# ActuatorMKII_Torpedoes.net
KiCad netlist of a schematic drawn in Altium Designer
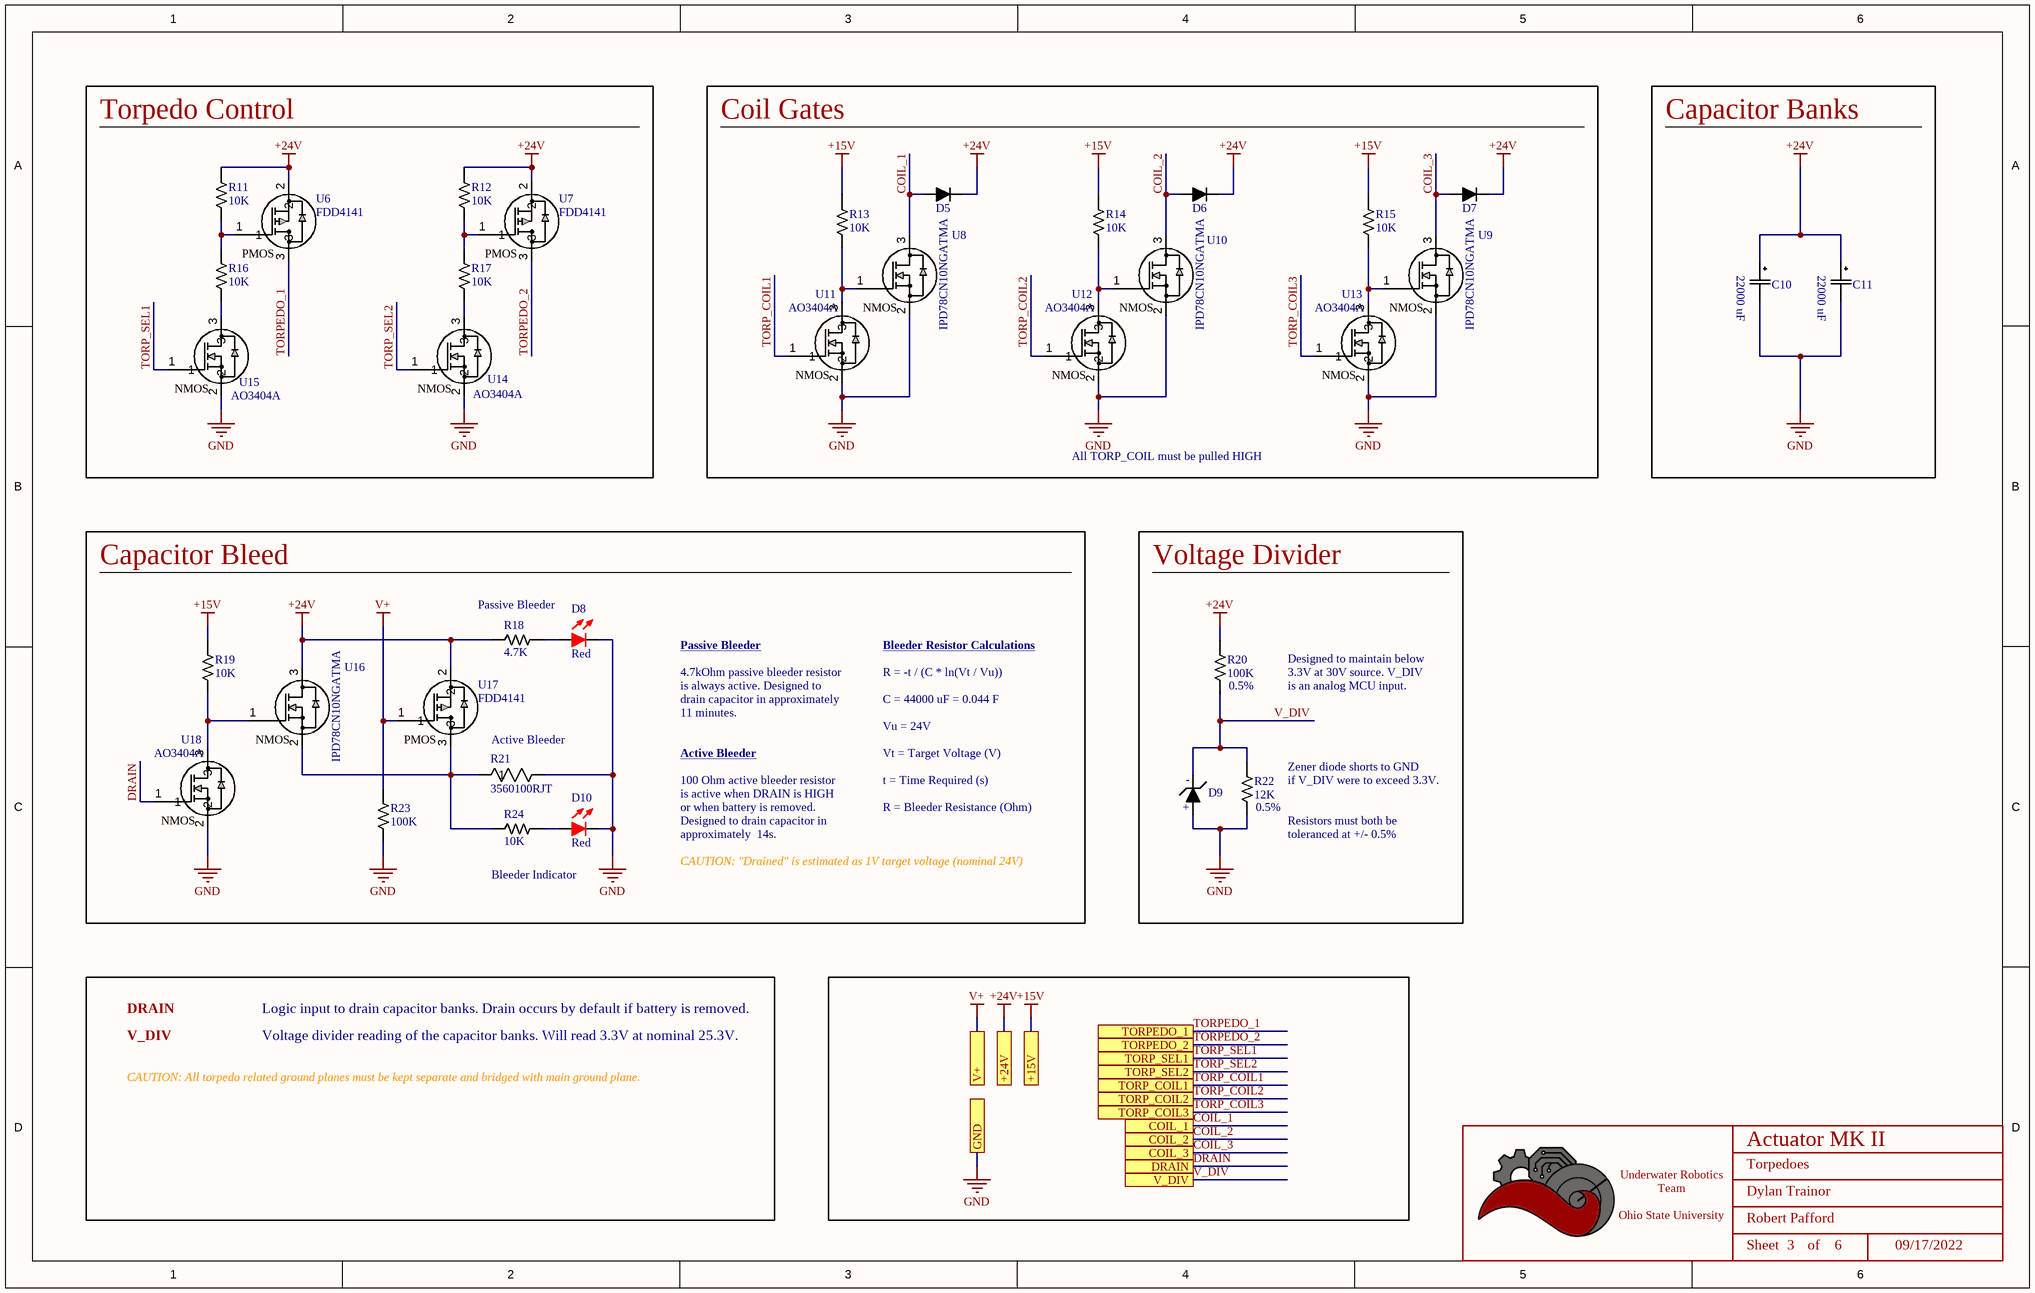
[diagram p0: ActuatorMKII_Torpedoes.SchDoc]

(export (version "E")
  (design (tool "Eeschema 10.0.6"))
  (components
    (comp (ref "C10")
      (value "Cap 22000uF 22V +/-20% Aluminum")
      (footprint "UVK1E223MRD_RA")
      (description "Cap 22000uF 25V 20% Aluminum Radial Through Hole")
      (fields (field (name "MADE BY") "Cole Davis") (field (name "VERIFIED BY") "Name"))
      (libsource (lib "Capacitors") (part "CAPACITOR_22000uF_Radial"))
    )
    (comp (ref "C11")
      (value "Cap 22000uF 22V +/-20% Aluminum")
      (footprint "UVK1E223MRD_RA")
      (description "Cap 22000uF 25V 20% Aluminum Radial Through Hole")
      (fields (field (name "MADE BY") "Cole Davis") (field (name "VERIFIED BY") "Name"))
      (libsource (lib "Capacitors") (part "CAPACITOR_22000uF_Radial"))
    )
    (comp (ref "D5")
      (value "B330-13-F")
      (footprint "DO-214AB")
      (description "Schottky Diode, 30V reverse breakdown, 3A, Vf = 0.500V")
      (fields (field (name "MADE BY") "Tyson N."))
      (libsource (lib "Diodes") (part "SCHOTTKY_30V_3A"))
    )
    (comp (ref "D6")
      (value "B330-13-F")
      (footprint "DO-214AB")
      (description "Schottky Diode, 30V reverse breakdown, 3A, Vf = 0.500V")
      (fields (field (name "MADE BY") "Tyson N."))
      (libsource (lib "Diodes") (part "SCHOTTKY_30V_3A"))
    )
    (comp (ref "D7")
      (value "B330-13-F")
      (footprint "DO-214AB")
      (description "Schottky Diode, 30V reverse breakdown, 3A, Vf = 0.500V")
      (fields (field (name "MADE BY") "Tyson N."))
      (libsource (lib "Diodes") (part "SCHOTTKY_30V_3A"))
    )
    (comp (ref "D8")
      (value "150060RS75000")
      (footprint "LED_0603")
      (description "LED Red Vf= 2V If = 0.020A\r\n150060RS75000")
      (fields (field (name "COLOR") "Red") (field (name "MADE BY") "Robert Pafford"))
      (libsource (lib "Diodes") (part "LED_Red_0603"))
    )
    (comp (ref "D9")
      (value "Zener_Diode_3.3V_250mW_1")
      (footprint "SOD-123")
      (description "Zener Diode ¦ 3.3 V ¦ 250 mW ¦ SOT-23")
      (fields (field (name "POWER") "410mW") (field (name "MADE BY") "Nathan A"))
      (libsource (lib "Diodes") (part "Zener_Diode_3.3V_250mW_1"))
    )
    (comp (ref "D10")
      (value "150060RS75000")
      (footprint "LED_0603")
      (description "LED Red Vf= 2V If = 0.020A\r\n150060RS75000")
      (fields (field (name "COLOR") "Red") (field (name "MADE BY") "Robert Pafford"))
      (libsource (lib "Diodes") (part "LED_Red_0603"))
    )
    (comp (ref "R11")
      (value "10k Ohm 5% 1/10W")
      (footprint "RESISTOR_0603")
      (description "RES 10k OHM 5% 1/10W 0603")
      (fields
        (field (name "TOLERANCE") "+/- 5%")
        (field (name "VALUE  (OHMS)") "10K")
        (field (name "MADE BY") "Robert Pafford")
      )
      (libsource (lib "Resistors") (part "RESISTOR_10K_0603"))
    )
    (comp (ref "R12")
      (value "10k Ohm 5% 1/10W")
      (footprint "RESISTOR_0603")
      (description "RES 10k OHM 5% 1/10W 0603")
      (fields
        (field (name "TOLERANCE") "+/- 5%")
        (field (name "VALUE  (OHMS)") "10K")
        (field (name "MADE BY") "Robert Pafford")
      )
      (libsource (lib "Resistors") (part "RESISTOR_10K_0603"))
    )
    (comp (ref "R13")
      (value "10k Ohm 5% 1/10W")
      (footprint "RESISTOR_0603")
      (description "RES 10k OHM 5% 1/10W 0603")
      (fields
        (field (name "TOLERANCE") "+/- 5%")
        (field (name "VALUE  (OHMS)") "10K")
        (field (name "MADE BY") "Robert Pafford")
      )
      (libsource (lib "Resistors") (part "RESISTOR_10K_0603"))
    )
    (comp (ref "R14")
      (value "10k Ohm 5% 1/10W")
      (footprint "RESISTOR_0603")
      (description "RES 10k OHM 5% 1/10W 0603")
      (fields
        (field (name "TOLERANCE") "+/- 5%")
        (field (name "VALUE  (OHMS)") "10K")
        (field (name "MADE BY") "Robert Pafford")
      )
      (libsource (lib "Resistors") (part "RESISTOR_10K_0603"))
    )
    (comp (ref "R15")
      (value "10k Ohm 5% 1/10W")
      (footprint "RESISTOR_0603")
      (description "RES 10k OHM 5% 1/10W 0603")
      (fields
        (field (name "TOLERANCE") "+/- 5%")
        (field (name "VALUE  (OHMS)") "10K")
        (field (name "MADE BY") "Robert Pafford")
      )
      (libsource (lib "Resistors") (part "RESISTOR_10K_0603"))
    )
    (comp (ref "R16")
      (value "10k Ohm 5% 1/10W")
      (footprint "RESISTOR_0603")
      (description "RES 10k OHM 5% 1/10W 0603")
      (fields
        (field (name "TOLERANCE") "+/- 5%")
        (field (name "VALUE  (OHMS)") "10K")
        (field (name "MADE BY") "Robert Pafford")
      )
      (libsource (lib "Resistors") (part "RESISTOR_10K_0603"))
    )
    (comp (ref "R17")
      (value "10k Ohm 5% 1/10W")
      (footprint "RESISTOR_0603")
      (description "RES 10k OHM 5% 1/10W 0603")
      (fields
        (field (name "TOLERANCE") "+/- 5%")
        (field (name "VALUE  (OHMS)") "10K")
        (field (name "MADE BY") "Robert Pafford")
      )
      (libsource (lib "Resistors") (part "RESISTOR_10K_0603"))
    )
    (comp (ref "R18")
      (value "4.7k Ohm 5% 1/10W")
      (footprint "RESISTOR_0603")
      (description "RES 4.7k OHM 5% 1/10W 0603")
      (fields
        (field (name "TOLERANCE") "+/- 5%")
        (field (name "VALUE  (OHMS)") "4.7K")
        (field (name "MADE BY") "Robert Pafford")
      )
      (libsource (lib "Resistors") (part "RESISTOR_4.7K_0603"))
    )
    (comp (ref "R19")
      (value "10k Ohm 5% 1/10W")
      (footprint "RESISTOR_0603")
      (description "RES 10k OHM 5% 1/10W 0603")
      (fields
        (field (name "TOLERANCE") "+/- 5%")
        (field (name "VALUE  (OHMS)") "10K")
        (field (name "MADE BY") "Robert Pafford")
      )
      (libsource (lib "Resistors") (part "RESISTOR_10K_0603"))
    )
    (comp (ref "R20")
      (value "100k Ohm 0.5% 1/10W")
      (footprint "RESISTOR_0603")
      (description "RES 100k OHM 0.5% 1/10W 0603")
      (fields
        (field (name "TOLERANCE") "+/- 0.5%")
        (field (name "VALUE  (OHMS)") "100K")
        (field (name "MADE BY") "John Ulm")
      )
      (libsource (lib "Resistors") (part "RESISTOR_100K_0.5%_0603"))
    )
    (comp (ref "R21")
      (value "3560100RJT")
      (footprint "RES_3550_TEC")
      (description "RES 35601 100R 6W 5%")
      (fields
        (field (name "MANUFACTURER_PART_NUMBER") "3550120RJT")
        (field (name "COPYRIGHT") "Copyright (C) 2022 Ultra Librarian. All rights reserved.")
      )
      (libsource (lib "Resistors") (part "3560100RJT"))
    )
    (comp (ref "R22")
      (value "12k Ohm 0.5% 1/10W")
      (footprint "RESISTOR_0603")
      (description "RES 12k OHM 0.5% 1/10W 0603")
      (fields
        (field (name "TOLERANCE") "+/- 0.5%")
        (field (name "VALUE  (OHMS)") "12K")
        (field (name "MADE BY") "John Ulm")
      )
      (libsource (lib "Resistors") (part "RESISTOR_12K_0.5%_0603"))
    )
    (comp (ref "R23")
      (value "100k Ohm 5% 1/8W")
      (footprint "RESISTOR_0603")
      (description "RES 100k OHM 5% 1/10W 0603")
      (fields
        (field (name "TOLERANCE") "+/- 5%")
        (field (name "VALUE  (OHMS)") "100K")
        (field (name "MADE BY") "Flip B")
      )
      (libsource (lib "Resistors") (part "RESISTOR_100K_0603_1"))
    )
    (comp (ref "R24")
      (value "10k Ohm 5% 1/10W")
      (footprint "RESISTOR_0603")
      (description "RES 10k OHM 5% 1/10W 0603")
      (fields
        (field (name "TOLERANCE") "+/- 5%")
        (field (name "VALUE  (OHMS)") "10K")
        (field (name "MADE BY") "Robert Pafford")
      )
      (libsource (lib "Resistors") (part "RESISTOR_10K_0603"))
    )
    (comp (ref "U6")
      (value "FDD4141")
      (footprint "DPAK_ONS")
      (description "P-Channel 10.8A (Ta), 50A (Tc) 2.4W (Ta), 69W (Tc) Surface Mount D-PAK (TO-252AA)")
      (fields (field (name "CREATED BY") "Dylan T"))
      (libsource (lib "Transistors") (part "FDD4141"))
    )
    (comp (ref "U7")
      (value "FDD4141")
      (footprint "DPAK_ONS")
      (description "P-Channel 10.8A (Ta), 50A (Tc) 2.4W (Ta), 69W (Tc) Surface Mount D-PAK (TO-252AA)")
      (fields (field (name "CREATED BY") "Dylan T"))
      (libsource (lib "Transistors") (part "FDD4141"))
    )
    (comp (ref "U8")
      (value "MOSFET N-Ch 100V 13A TO252-3")
      (footprint "DPAK_ONS")
      (description "N-Channel 100 V 13A (Tc) 31W (Tc) Surface Mount PG-TO252-3")
      (fields (field (name "CREATED BY") "John Ulm") (field (name "VERIFIED BY") "----"))
      (libsource (lib "Transistors") (part "IPD78CN10NGATMA1"))
    )
    (comp (ref "U9")
      (value "MOSFET N-Ch 100V 13A TO252-3")
      (footprint "DPAK_ONS")
      (description "N-Channel 100 V 13A (Tc) 31W (Tc) Surface Mount PG-TO252-3")
      (fields (field (name "CREATED BY") "John Ulm") (field (name "VERIFIED BY") "----"))
      (libsource (lib "Transistors") (part "IPD78CN10NGATMA1"))
    )
    (comp (ref "U10")
      (value "MOSFET N-Ch 100V 13A TO252-3")
      (footprint "DPAK_ONS")
      (description "N-Channel 100 V 13A (Tc) 31W (Tc) Surface Mount PG-TO252-3")
      (fields (field (name "CREATED BY") "John Ulm") (field (name "VERIFIED BY") "----"))
      (libsource (lib "Transistors") (part "IPD78CN10NGATMA1"))
    )
    (comp (ref "U11")
      (value "AO3404A")
      (footprint "SOT-23-3")
      (description "N-Channel 30 V 5.8A (Ta) 1.4W (Ta) Surface Mount SOT-23-3")
      (fields (field (name "CREATED BY") "Dylan T"))
      (libsource (lib "Transistors") (part "AO3404A"))
    )
    (comp (ref "U12")
      (value "AO3404A")
      (footprint "SOT-23-3")
      (description "N-Channel 30 V 5.8A (Ta) 1.4W (Ta) Surface Mount SOT-23-3")
      (fields (field (name "CREATED BY") "Dylan T"))
      (libsource (lib "Transistors") (part "AO3404A"))
    )
    (comp (ref "U13")
      (value "AO3404A")
      (footprint "SOT-23-3")
      (description "N-Channel 30 V 5.8A (Ta) 1.4W (Ta) Surface Mount SOT-23-3")
      (fields (field (name "CREATED BY") "Dylan T"))
      (libsource (lib "Transistors") (part "AO3404A"))
    )
    (comp (ref "U14")
      (value "AO3404A")
      (footprint "SOT-23-3")
      (description "N-Channel 30 V 5.8A (Ta) 1.4W (Ta) Surface Mount SOT-23-3")
      (fields (field (name "CREATED BY") "Dylan T"))
      (libsource (lib "Transistors") (part "AO3404A"))
    )
    (comp (ref "U15")
      (value "AO3404A")
      (footprint "SOT-23-3")
      (description "N-Channel 30 V 5.8A (Ta) 1.4W (Ta) Surface Mount SOT-23-3")
      (fields (field (name "CREATED BY") "Dylan T"))
      (libsource (lib "Transistors") (part "AO3404A"))
    )
    (comp (ref "U16")
      (value "MOSFET N-Ch 100V 13A TO252-3")
      (footprint "DPAK_ONS")
      (description "N-Channel 100 V 13A (Tc) 31W (Tc) Surface Mount PG-TO252-3")
      (fields (field (name "CREATED BY") "John Ulm") (field (name "VERIFIED BY") "----"))
      (libsource (lib "Transistors") (part "IPD78CN10NGATMA1"))
    )
    (comp (ref "U17")
      (value "FDD4141")
      (footprint "DPAK_ONS")
      (description "P-Channel 10.8A (Ta), 50A (Tc) 2.4W (Ta), 69W (Tc) Surface Mount D-PAK (TO-252AA)")
      (fields (field (name "CREATED BY") "Dylan T"))
      (libsource (lib "Transistors") (part "FDD4141"))
    )
    (comp (ref "U18")
      (value "AO3404A")
      (footprint "SOT-23-3")
      (description "N-Channel 30 V 5.8A (Ta) 1.4W (Ta) Surface Mount SOT-23-3")
      (fields (field (name "CREATED BY") "Dylan T"))
      (libsource (lib "Transistors") (part "AO3404A"))
    )
  )
  (nets
    (net (code "1") (name "+15V") (class "Default")
      (node (ref "R13") (pin "1") (pinfunction "1_1") (pintype "passive"))
      (node (ref "R14") (pin "1") (pinfunction "1_1") (pintype "passive"))
      (node (ref "R15") (pin "1") (pinfunction "1_1") (pintype "passive"))
      (node (ref "R19") (pin "1") (pinfunction "1_1") (pintype "passive"))
    )
    (net (code "2") (name "+24V") (class "Default")
      (node (ref "C10") (pin "1") (pinfunction "1_1") (pintype "passive"))
      (node (ref "C11") (pin "1") (pinfunction "1_1") (pintype "passive"))
      (node (ref "D5") (pin "2") (pinfunction "2_2") (pintype "passive"))
      (node (ref "D6") (pin "2") (pinfunction "2_2") (pintype "passive"))
      (node (ref "D7") (pin "2") (pinfunction "2_2") (pintype "passive"))
      (node (ref "R11") (pin "1") (pinfunction "1_1") (pintype "passive"))
      (node (ref "R12") (pin "1") (pinfunction "1_1") (pintype "passive"))
      (node (ref "R18") (pin "2") (pinfunction "2_2") (pintype "passive"))
      (node (ref "R20") (pin "1") (pinfunction "1_1") (pintype "passive"))
      (node (ref "U16") (pin "3") (pinfunction "3_3") (pintype "passive"))
      (node (ref "U17") (pin "2") (pinfunction "2_2") (pintype "passive"))
      (node (ref "U6") (pin "2") (pinfunction "2_2") (pintype "passive"))
      (node (ref "U7") (pin "2") (pinfunction "2_2") (pintype "passive"))
    )
    (net (code "3") (name "/COIL_1") (class "Default")
      (node (ref "D5") (pin "1") (pinfunction "1_1") (pintype "passive"))
      (node (ref "U8") (pin "3") (pinfunction "3_3") (pintype "passive"))
    )
    (net (code "4") (name "/COIL_2") (class "Default")
      (node (ref "D6") (pin "1") (pinfunction "1_1") (pintype "passive"))
      (node (ref "U10") (pin "3") (pinfunction "3_3") (pintype "passive"))
    )
    (net (code "5") (name "/COIL_3") (class "Default")
      (node (ref "D7") (pin "1") (pinfunction "1_1") (pintype "passive"))
      (node (ref "U9") (pin "3") (pinfunction "3_3") (pintype "passive"))
    )
    (net (code "6") (name "/DRAIN") (class "Default")
      (node (ref "U18") (pin "1") (pinfunction "1_1") (pintype "passive"))
    )
    (net (code "7") (name "/TORPEDO_1") (class "Default")
      (node (ref "U6") (pin "3") (pinfunction "3_3") (pintype "passive"))
    )
    (net (code "8") (name "/TORPEDO_2") (class "Default")
      (node (ref "U7") (pin "3") (pinfunction "3_3") (pintype "passive"))
    )
    (net (code "9") (name "/TORP_COIL1") (class "Default")
      (node (ref "U11") (pin "1") (pinfunction "1_1") (pintype "passive"))
    )
    (net (code "10") (name "/TORP_COIL2") (class "Default")
      (node (ref "U12") (pin "1") (pinfunction "1_1") (pintype "passive"))
    )
    (net (code "11") (name "/TORP_COIL3") (class "Default")
      (node (ref "U13") (pin "1") (pinfunction "1_1") (pintype "passive"))
    )
    (net (code "12") (name "/TORP_SEL1") (class "Default")
      (node (ref "U15") (pin "1") (pinfunction "1_1") (pintype "passive"))
    )
    (net (code "13") (name "/TORP_SEL2") (class "Default")
      (node (ref "U14") (pin "1") (pinfunction "1_1") (pintype "passive"))
    )
    (net (code "14") (name "/V_DIV") (class "Default")
      (node (ref "D9") (pin "2") (pinfunction "2_2") (pintype "passive"))
      (node (ref "R20") (pin "2") (pinfunction "2_2") (pintype "passive"))
      (node (ref "R22") (pin "1") (pinfunction "1_1") (pintype "passive"))
    )
    (net (code "15") (name "GND") (class "Default")
      (node (ref "C10") (pin "2") (pinfunction "2_2") (pintype "passive"))
      (node (ref "C11") (pin "2") (pinfunction "2_2") (pintype "passive"))
      (node (ref "D10") (pin "2") (pinfunction "2_2") (pintype "passive"))
      (node (ref "D8") (pin "2") (pinfunction "2_2") (pintype "passive"))
      (node (ref "D9") (pin "1") (pinfunction "1_1") (pintype "passive"))
      (node (ref "R21") (pin "2") (pinfunction "2_2") (pintype "passive"))
      (node (ref "R22") (pin "2") (pinfunction "2_2") (pintype "passive"))
      (node (ref "R23") (pin "2") (pinfunction "2_2") (pintype "passive"))
      (node (ref "U10") (pin "2") (pinfunction "2_2") (pintype "passive"))
      (node (ref "U11") (pin "2") (pinfunction "2_2") (pintype "passive"))
      (node (ref "U12") (pin "2") (pinfunction "2_2") (pintype "passive"))
      (node (ref "U13") (pin "2") (pinfunction "2_2") (pintype "passive"))
      (node (ref "U14") (pin "2") (pinfunction "2_2") (pintype "passive"))
      (node (ref "U15") (pin "2") (pinfunction "2_2") (pintype "passive"))
      (node (ref "U18") (pin "2") (pinfunction "2_2") (pintype "passive"))
      (node (ref "U8") (pin "2") (pinfunction "2_2") (pintype "passive"))
      (node (ref "U9") (pin "2") (pinfunction "2_2") (pintype "passive"))
    )
    (net (code "16") (name "Net-(D8-Pad1)") (class "Default")
      (node (ref "D8") (pin "1") (pinfunction "1_1") (pintype "passive"))
      (node (ref "R18") (pin "1") (pinfunction "1_1") (pintype "passive"))
    )
    (net (code "17") (name "Net-(D10-Pad1)") (class "Default")
      (node (ref "D10") (pin "1") (pinfunction "1_1") (pintype "passive"))
      (node (ref "R24") (pin "1") (pinfunction "1_1") (pintype "passive"))
    )
    (net (code "18") (name "Net-(R11-Pad2)") (class "Default")
      (node (ref "R11") (pin "2") (pinfunction "2_2") (pintype "passive"))
      (node (ref "R16") (pin "1") (pinfunction "1_1") (pintype "passive"))
      (node (ref "U6") (pin "1") (pinfunction "1_1") (pintype "passive"))
    )
    (net (code "19") (name "Net-(R12-Pad2)") (class "Default")
      (node (ref "R12") (pin "2") (pinfunction "2_2") (pintype "passive"))
      (node (ref "R17") (pin "1") (pinfunction "1_1") (pintype "passive"))
      (node (ref "U7") (pin "1") (pinfunction "1_1") (pintype "passive"))
    )
    (net (code "20") (name "Net-(R13-Pad2)") (class "Default")
      (node (ref "R13") (pin "2") (pinfunction "2_2") (pintype "passive"))
      (node (ref "U11") (pin "3") (pinfunction "3_3") (pintype "passive"))
      (node (ref "U8") (pin "1") (pinfunction "1_1") (pintype "passive"))
    )
    (net (code "21") (name "Net-(R14-Pad2)") (class "Default")
      (node (ref "R14") (pin "2") (pinfunction "2_2") (pintype "passive"))
      (node (ref "U10") (pin "1") (pinfunction "1_1") (pintype "passive"))
      (node (ref "U12") (pin "3") (pinfunction "3_3") (pintype "passive"))
    )
    (net (code "22") (name "Net-(R15-Pad2)") (class "Default")
      (node (ref "R15") (pin "2") (pinfunction "2_2") (pintype "passive"))
      (node (ref "U13") (pin "3") (pinfunction "3_3") (pintype "passive"))
      (node (ref "U9") (pin "1") (pinfunction "1_1") (pintype "passive"))
    )
    (net (code "23") (name "Net-(R16-Pad2)") (class "Default")
      (node (ref "R16") (pin "2") (pinfunction "2_2") (pintype "passive"))
      (node (ref "U15") (pin "3") (pinfunction "3_3") (pintype "passive"))
    )
    (net (code "24") (name "Net-(R17-Pad2)") (class "Default")
      (node (ref "R17") (pin "2") (pinfunction "2_2") (pintype "passive"))
      (node (ref "U14") (pin "3") (pinfunction "3_3") (pintype "passive"))
    )
    (net (code "25") (name "Net-(R19-Pad2)") (class "Default")
      (node (ref "R19") (pin "2") (pinfunction "2_2") (pintype "passive"))
      (node (ref "U16") (pin "1") (pinfunction "1_1") (pintype "passive"))
      (node (ref "U18") (pin "3") (pinfunction "3_3") (pintype "passive"))
    )
    (net (code "26") (name "Net-(R21-Pad1)") (class "Default")
      (node (ref "R21") (pin "1") (pinfunction "1_1") (pintype "passive"))
      (node (ref "R24") (pin "2") (pinfunction "2_2") (pintype "passive"))
      (node (ref "U16") (pin "2") (pinfunction "2_2") (pintype "passive"))
      (node (ref "U17") (pin "3") (pinfunction "3_3") (pintype "passive"))
    )
    (net (code "27") (name "V+") (class "Default")
      (node (ref "R23") (pin "1") (pinfunction "1_1") (pintype "passive"))
      (node (ref "U17") (pin "1") (pinfunction "1_1") (pintype "passive"))
    )
  )
)
